# AIRZAI_LID_BD_REVC_Sheet1.net
KiCad netlist of a schematic drawn in Altium Designer
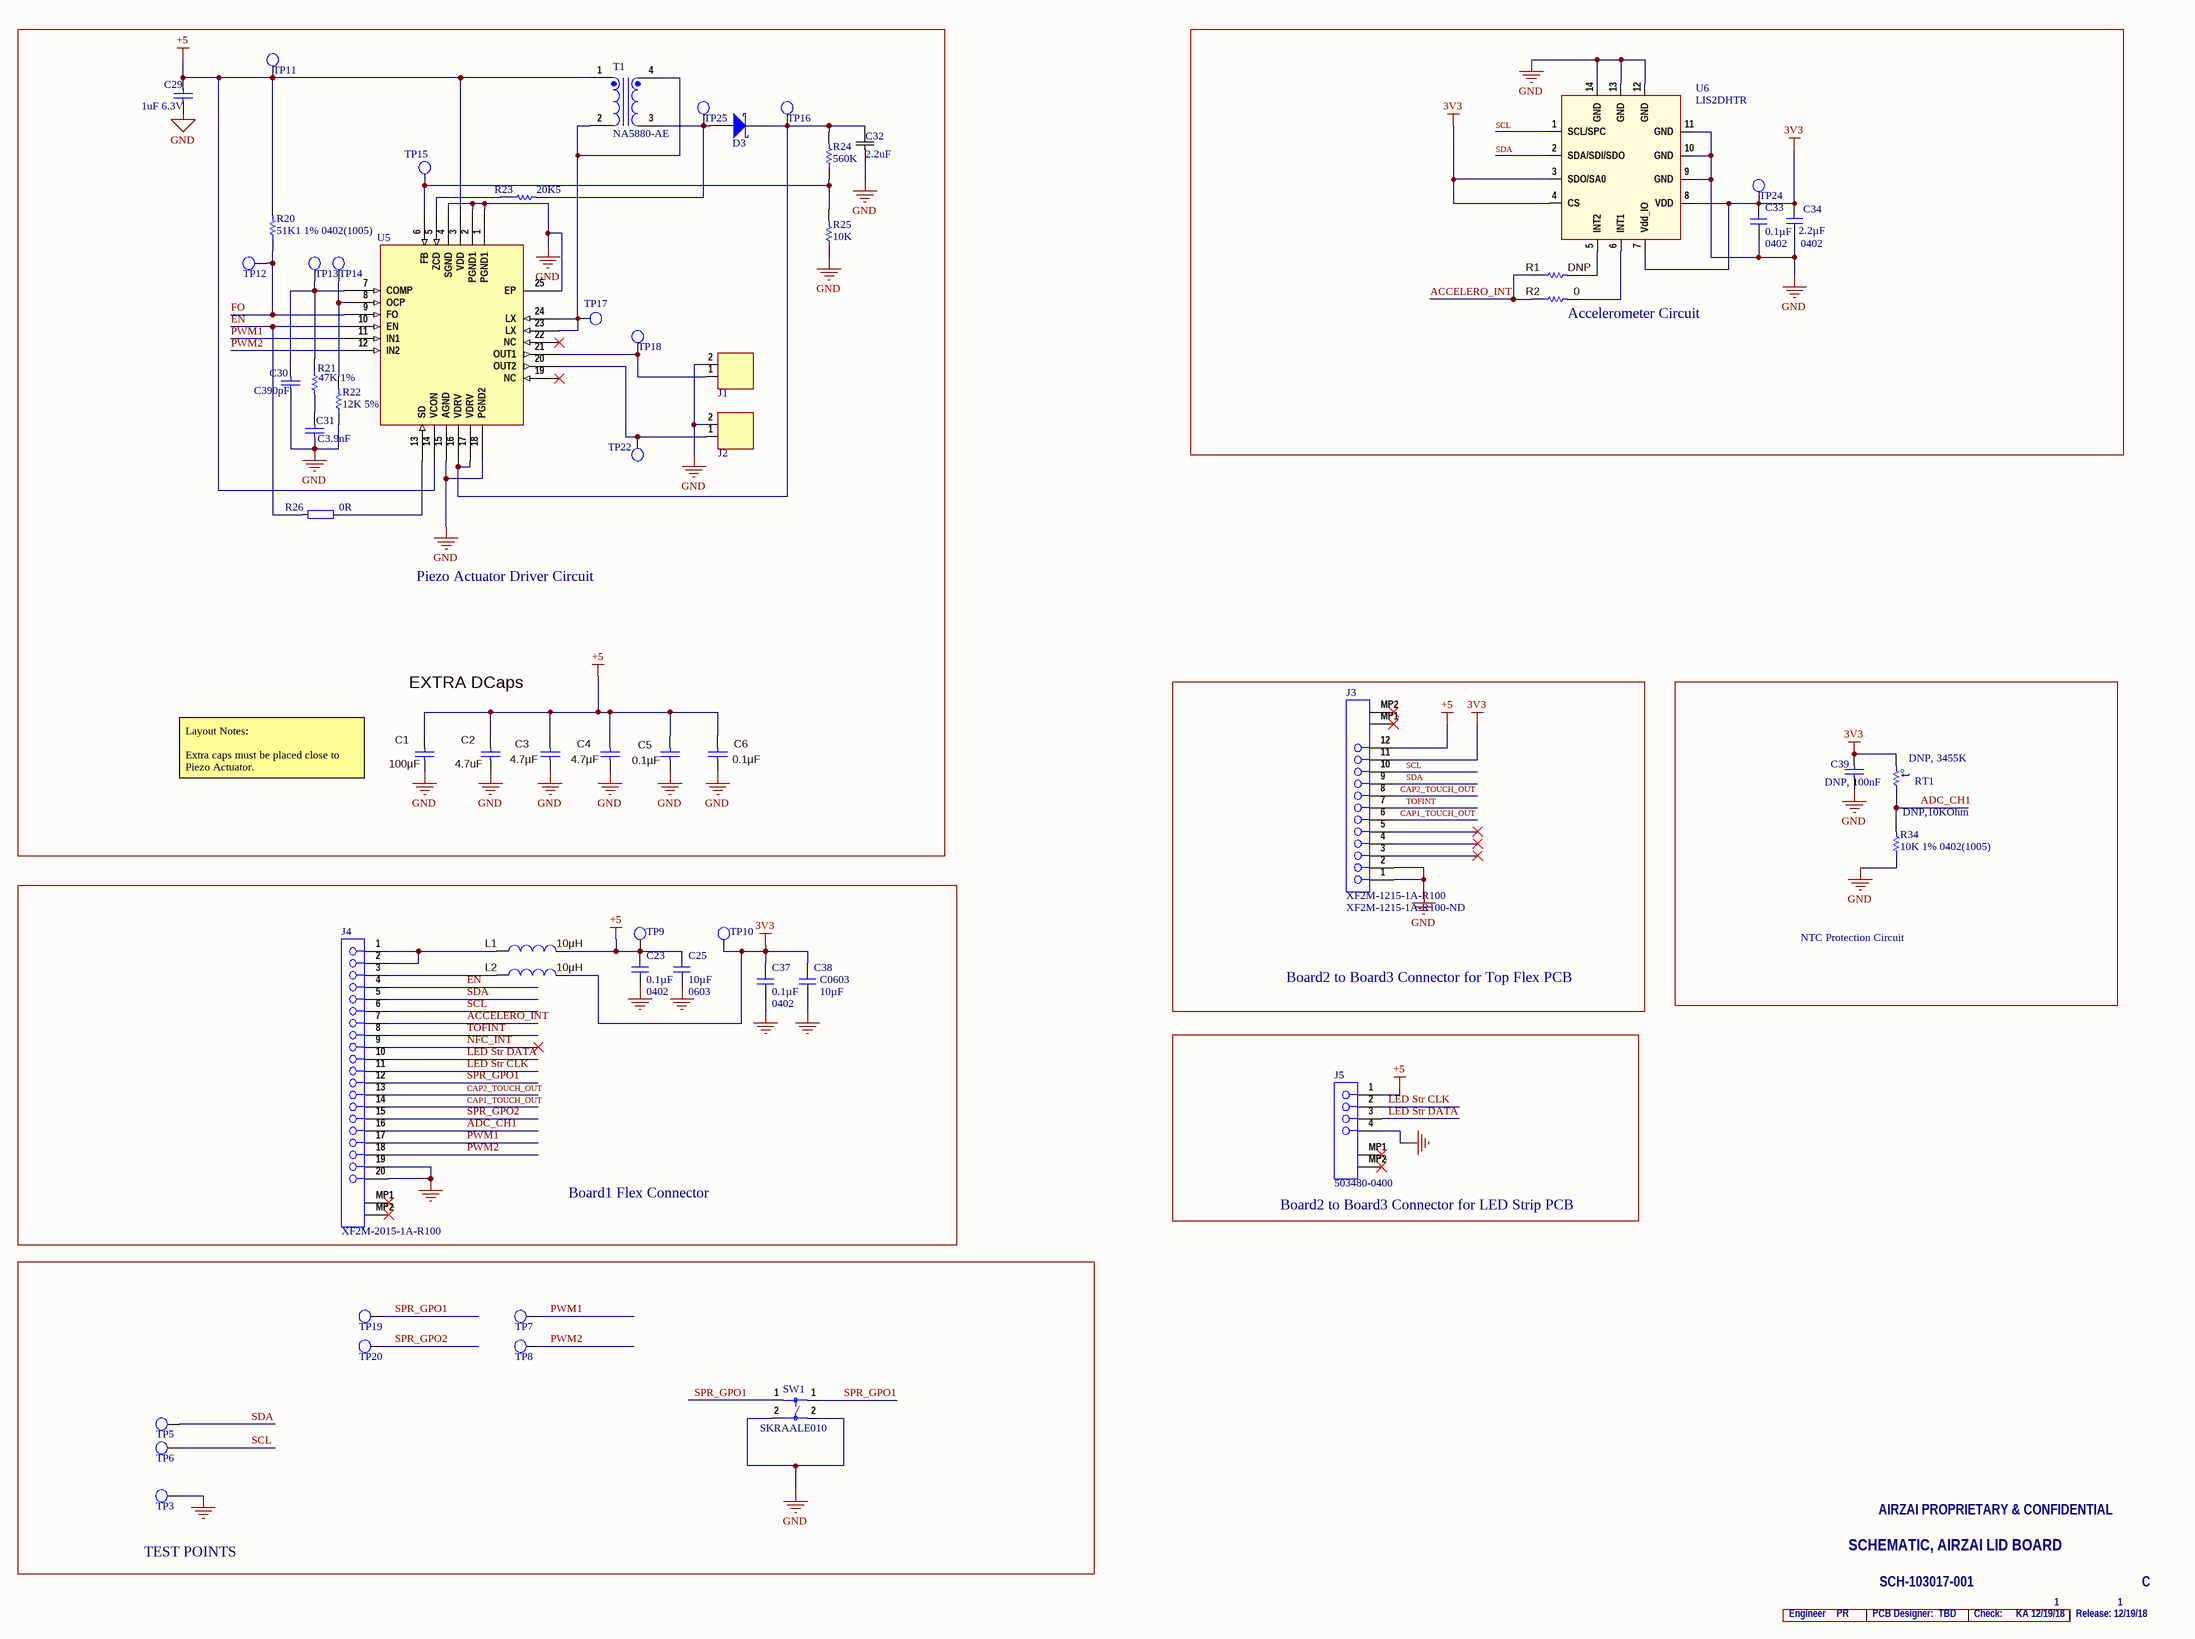
[diagram p0: AIRZAI_LID_BD_REVC Sheet1.SchDoc]

(export (version "E")
  (design (tool "Eeschema 10.0.6"))
  (components
    (comp (ref "C1")
      (value "GRM31CR60J107ME39L")
      (footprint "1206_180")
      (description "CAP, CERM, 100 µF, 6.3 V, +/- 20%, X5R, 1206")
      (fields
        (field (name "VALUEDISPLAYED") "100µF")
        (field (name "MANUFACTURER") "MuRata")
        (field (name "PUBLISHER") "Texas Instruments")
      )
      (libsource (lib "Capacitor_Ceramic") (part "GRM31CR60J107ME39L"))
    )
    (comp (ref "C2")
      (value "4.7uF")
      (footprint "SM0402_BTD.1SM_ACT_H55_CAP_WSS")
      (description "CAP, CERM, 4.7 µF, 6.3 V, +/- 20%, X5R, 0402")
      (fields (field (name "PARTNUMBER") "C1005X5R0J475M050BC") (field (name "MANUFACTURER") "TDK"))
      (libsource (lib "Capacitor_Ceramic") (part "C1005X5R0J475M050BC"))
    )
    (comp (ref "C3")
      (value "C1005X5R0J475M050BC")
      (footprint "SM0402_BTD.1SM_ACT_H55_CAP_WSS")
      (description "CAP, CERM, 4.7 µF, 6.3 V, +/- 20%, X5R, 0402")
      (fields
        (field (name "VALUEDISPLAYED") "4.7µF")
        (field (name "MANUFACTURER") "TDK")
        (field (name "PUBLISHER") "Texas Instruments")
      )
      (libsource (lib "Capacitor_Ceramic") (part "C1005X5R0J475M050BC"))
    )
    (comp (ref "C4")
      (value "C1005X5R0J475M050BC")
      (footprint "SM0402_BTD.1SM_ACT_H55_CAP_WSS")
      (description "CAP, CERM, 4.7 µF, 6.3 V, +/- 20%, X5R, 0402")
      (fields
        (field (name "VALUEDISPLAYED") "4.7µF")
        (field (name "MANUFACTURER") "TDK")
        (field (name "PUBLISHER") "Texas Instruments")
      )
      (libsource (lib "Capacitor_Ceramic") (part "C1005X5R0J475M050BC"))
    )
    (comp (ref "C5")
      (value "C1005X5R1A104K050BA")
      (footprint "SM0402_BTD.1SM_ACT_H55_CAP_WSS")
      (description "CAP, CERM, 0.1 µF, 10 V, +/- 10%, X5R, 0402")
      (fields
        (field (name "VALUEDISPLAYED") "0.1µF")
        (field (name "MANUFACTURER") "TDK")
        (field (name "PUBLISHER") "Texas Instruments")
      )
      (libsource (lib "Capacitor_Ceramic") (part "C1005X5R1A104K050BA"))
    )
    (comp (ref "C6")
      (value "C1005X5R1A104K050BA")
      (footprint "SM0402_BTD.1SM_ACT_H55_CAP_WSS")
      (description "CAP, CERM, 0.1 µF, 10 V, +/- 10%, X5R, 0402")
      (fields
        (field (name "VALUEDISPLAYED") "0.1µF")
        (field (name "MANUFACTURER") "TDK")
        (field (name "PUBLISHER") "Texas Instruments")
      )
      (libsource (lib "Capacitor_Ceramic") (part "C1005X5R1A104K050BA"))
    )
    (comp (ref "C23")
      (value "0.1µF")
      (footprint "0402")
      (description "Capacitor, X7R, ±10%")
      (fields (field (name "MANUFACTURER") "TDK") (field (name "MANUFACTURER PART NUMBER") "C1005X7R1C104K"))
      (libsource (lib "Nordic Passive DB") (part "CAP"))
    )
    (comp (ref "C25")
      (value "10µF")
      (footprint "0603")
      (description "6.3volts X5R 20%")
      (fields
        (field (name "MANUFACTURER") "MURATA")
        (field (name "MANUFACTURER PART NUMBER") "GRM188R60J106ME47D")
      )
      (libsource (lib "Nordic Passive DB") (part "CAP"))
    )
    (comp (ref "C29")
      (value "1uF 6.3V")
      (footprint "CAPC0402(1005)60_M")
      (description "CAP 1uF 6.3V ±10% 0402 (1005 Metric) Thickness 0.6mm SMD")
      (fields (field (name "TOLERANCE") "Â±10%") (field (name "MANUFACTURER") "MURATA"))
      (libsource (lib "AIRZAI_LID_BD_REVA") (part "CAP"))
    )
    (comp (ref "C30")
      (value "C390pF")
      (footprint "CAPC0402(1005)60_M")
      (description "CAP 390pF 50V ±20% 0402 (1005 Metric) Thickness 0.6mm SMD")
      (fields (field (name "TOLERANCE") "Â±20%") (field (name "MANUFACTURER") "KEMET"))
      (libsource (lib "") (part "CAP_1"))
    )
    (comp (ref "C31")
      (value "C3.9nF")
      (footprint "CAPC0402(1005)60_M")
      (description "CAP 3.9nF 50V ±10% 0402 (1005 Metric) Thickness 0.6mm SMD")
      (fields (field (name "TOLERANCE") "Â±10%") (field (name "MANUFACTURER") "TDK"))
      (libsource (lib "AIRZAI_LID_BD_REVA") (part "CAP"))
    )
    (comp (ref "C32")
      (value "2.2uF")
      (footprint "C1210_N")
      (description "Imported")
      (fields
        (field (name "MANUFACTURER_PART_NUMBER") "C3225JB2A225K230AB")
        (field (name "MANUFACTURER") "TDK")
      )
      (libsource (lib "C3225JB2A225K230AB") (part "C3225JB2A225K230"))
    )
    (comp (ref "C33")
      (value "0.1µF")
      (footprint "0402")
      (description "Capacitor, X7R, ±10%")
      (fields (field (name "MANUFACTURER") "TDK") (field (name "MANUFACTURER PART NUMBER") "C1005X7R1C104K"))
      (libsource (lib "Nordic Passive DB") (part "CAP"))
    )
    (comp (ref "C34")
      (value "2.2µF")
      (footprint "0402")
      (description "Capacitor, X7R, ±10%")
      (fields (field (name "MANUFACTURER") "TDK") (field (name "MANUFACTURER PART NUMBER") "C1005X5R0J225M"))
      (libsource (lib "Nordic Passive DB") (part "CAP"))
    )
    (comp (ref "C37")
      (value "0.1µF")
      (footprint "0402")
      (description "Capacitor, X7R, ±10%")
      (fields (field (name "MANUFACTURER") "TDK") (field (name "MANUFACTURER PART NUMBER") "C1005X7R1C104K"))
      (libsource (lib "Nordic Passive DB") (part "CAP"))
    )
    (comp (ref "C38")
      (value "10µF")
      (footprint "C0603")
      (description "Capacitor, X7R, ±10%")
      (fields
        (field (name "MANUFACTURER") "MURATA")
        (field (name "MANUFACTURER PART NUMBER") "GRM188R60J106ME47D")
      )
      (libsource (lib "Nordic Passive DB") (part "CAP"))
    )
    (comp (ref "C39")
      (value "DNP, 100nF")
      (footprint "CAPC0402(1005)60_M")
      (description "CAP 100nF 10V ±10% 0402 (1005 Metric) Thickness 0.6mm SMD")
      (fields (field (name "TOLERANCE") "Â±10%") (field (name "MANUFACTURER") "Yageo"))
      (libsource (lib "AIRZAI_LID_BD_REVA") (part "CAP"))
    )
    (comp (ref "D3")
      (value "STPS2H100A")
      (footprint "STM-SMA-2_V")
      (description "Power Schottky Rectifier, 2 A, 100 V, 2-Pin SMD (SMA), RoHS, Tape and Reel")
      (fields (field (name "MANUFACTURER") "STMicroelectronics"))
      (libsource (lib "AIRZAI_LID_BD_REVA") (part "DSKY-AK-2"))
    )
    (comp (ref "J1")
      (value "~")
      (footprint "CON_78171_0002")
      (fields (field (name "MANUFACTURER PART NUMBER") "781710002") (field (name "MANUFACTURER") "MOLEX"))
      (libsource (lib "DFM_JBKEGSVS_Library") (part "CONN_BM02B_SURS_TF"))
    )
    (comp (ref "J2")
      (value "~")
      (footprint "CON_78171_0002")
      (fields (field (name "MANUFACTURER PART NUMBER") "781710002") (field (name "MANUFACTURER") "MOLEX"))
      (libsource (lib "DFM_JBKEGSVS_Library") (part "CONN_BM02B_SURS_TF"))
    )
    (comp (ref "J3")
      (value "XF2M-1215-1A-R100")
      (footprint "Omron_XF2M-1215-1A-R100")
      (description "12 Position FPC Connector Contacts, Top and Bottom 0.020\" (0.50mm) Surface Mount, Right Angle")
      (fields
        (field (name "MANUFACTURER") "Omron")
        (field (name "SUPPLIER PART NUMBER 1") "XF2M-1215-1A-R100-ND")
      )
      (libsource (lib "AIRZAI_LID_BD_REVA") (part "XF2M-1215-1A-R100"))
    )
    (comp (ref "J4")
      (value "XF2M-2015-1A-R100")
      (footprint "Omron_XF2M-2015-1A_0")
      (fields (field (name "MANUFACTURER") "OMRON ELECTRONIC COMPONENTS"))
      (libsource (lib "AIRZAI_LID_BD_REVA") (part "XF2M-2015-1A-R100"))
    )
    (comp (ref "J5")
      (value "503480-0400")
      (footprint "MOLX-503480-0400")
      (fields (field (name "MANUFACTURER") "Molex"))
      (libsource (lib "AIRZAI_LID_BD_REVA") (part "503480-0400"))
    )
    (comp (ref "L1")
      (value "CB2012T100KR")
      (footprint "0805")
      (description "Inductor, 10 µH, 0.5A, 0.65 ohm, SMD")
      (fields
        (field (name "MANUFACTURER") "Taiyo Yuden")
        (field (name "TOLERANCE") "10%")
        (field (name "VALUEDISPLAYED") "10µH")
      )
      (libsource (lib "AIRZAI_LED_SENSE_FLEX_REVA") (part "CB2012T100KR"))
    )
    (comp (ref "L2")
      (value "CB2012T100KR")
      (footprint "0805")
      (description "Inductor, 10 µH, 0.5A, 0.65 ohm, SMD")
      (fields
        (field (name "MANUFACTURER") "Taiyo Yuden")
        (field (name "TOLERANCE") "10%")
        (field (name "VALUEDISPLAYED") "10µH")
      )
      (libsource (lib "AIRZAI_LED_SENSE_FLEX_REVA") (part "CB2012T100KR"))
    )
    (comp (ref "R1")
      (value "DNP")
      (footprint "0402")
      (description "RES, DNP, 0402")
      (libsource (lib "Resistor_0402") (part "ERJ-2GE0R00X"))
    )
    (comp (ref "R2")
      (value "ERJ-2GE0R00X")
      (footprint "0402")
      (description "RES, 0, 5%, 0.063 W, 0402")
      (fields
        (field (name "VALUEDISPLAYED") "0")
        (field (name "MANUFACTURER") "Panasonic")
        (field (name "PUBLISHER") "Texas Instruments")
      )
      (libsource (lib "Resistor_0402") (part "ERJ-2GE0R00X"))
    )
    (comp (ref "R20")
      (value "51K1 1% 0402(1005)")
      (footprint "0402")
      (description "51K1 0.063W 1% 0402 (1005 Metric)  SMD")
      (fields (field (name "POWER") "0.063 W") (field (name "TOLERANCE") "1 %"))
      (libsource (lib "AIRZAI_LID_BD_REVA") (part "RES"))
    )
    (comp (ref "R21")
      (value "47K 1%")
      (footprint "0402")
      (description "47K 0.063W 1% 0402 (1005 Metric)  SMD")
      (fields (field (name "POWER") "0.063 W") (field (name "TOLERANCE") "1 %"))
      (libsource (lib "") (part "RES_2"))
    )
    (comp (ref "R22")
      (value "12K 5%")
      (footprint "0402")
      (description "12K 0.063W 5% 0402 (1005 Metric)  SMD")
      (fields (field (name "TOLERANCE") "5 %") (field (name "POWER") "0.063 W"))
      (libsource (lib "AIRZAI_LID_BD_REVA") (part "RES"))
    )
    (comp (ref "R23")
      (value "20K5")
      (footprint "0402")
      (description "20K5 0.063W 1% 0402 (1005 Metric)  SMD")
      (fields (field (name "POWER") "0.063 W") (field (name "TOLERANCE") "1 %"))
      (libsource (lib "") (part "RES_1"))
    )
    (comp (ref "R24")
      (value "560K")
      (footprint "0402")
      (description "560K 0.063W 1% 0402 (1005 Metric)  SMD")
      (fields (field (name "POWER") "0.063 W") (field (name "TOLERANCE") "1 %"))
      (libsource (lib "AIRZAI_LID_BD_REVA") (part "RES"))
    )
    (comp (ref "R25")
      (value "10K")
      (footprint "0402")
      (description "10K 0.063W 5% 0402 (1005 Metric)  SMD")
      (fields (field (name "TOLERANCE") "5 %") (field (name "POWER") "0.063 W"))
      (libsource (lib "AIRZAI_LID_BD_REVA") (part "RES"))
    )
    (comp (ref "R26")
      (value "0R")
      (footprint "0402")
      (description "Resistor, ±1%, 0.063W")
      (fields
        (field (name "MANUFACTURER") "Panasonic")
        (field (name "MANUFACTURER PART NUMBER") "ERJ-2GE0R00X")
      )
      (libsource (lib "Nordic Passive DB") (part "RES_1"))
    )
    (comp (ref "R34")
      (value "10K 1% 0402(1005)")
      (footprint "0402")
      (description "10K 0.063W 1% 0402 (1005 Metric)  SMD")
      (fields
        (field (name "ALTIUM_VALUE") "DNP,10KOhm")
        (field (name "TOLERANCE") "1 %")
        (field (name "POWER") "0.063 W")
      )
      (libsource (lib "AIRZAI_LID_BD_REVA") (part "RES"))
    )
    (comp (ref "RT1")
      (value "DNP, 3455K")
      (footprint "MURA-NCP18XH103F03RB-2_V")
      (description "NTC Thermistor, 10 KOhm, +/- 1%, 0.1 W, -40 to 125 degC, 0603 (1608 Metric), RoHS, Tape and Reel")
      (fields
        (field (name "MANUFACTURER") "Murata")
        (field (name "MANUFACTURER PART NUMBER") "NCP18XH103F03RB")
      )
      (libsource (lib "AIRZAI_LID_BD_REVA") (part "MURA-NCP18XH103F03RB-2"))
    )
    (comp (ref "SW1")
      (value "SKRAALE010")
      (footprint "SW_ALPS_SKRAALE010")
      (fields (field (name "MANUFACTURER") "ALPS") (field (name "MANUFACTURER PART NUMBER") "SKRAAKE010"))
      (libsource (lib "DFM_JBKEGSVS_Library") (part "SW_SKRAALE010"))
    )
    (comp (ref "T1")
      (value "NA5880-AE")
      (footprint "Coilcraft_NA5880-AE_MFG")
      (fields (field (name "MANUFACTURER") "CoilCraft") (field (name "TOLERANCE") "20%"))
      (libsource (lib "AIRZAI_LID_BD_REVA") (part "TRANS-DOT-1-1-4"))
    )
    (comp (ref "TP3")
      (value "TESTPOINT")
      (footprint "TP_0.9MM")
      (libsource (lib "DFM_JBKEGSVS_Library") (part "TESTPOINT"))
    )
    (comp (ref "TP5")
      (value "TESTPOINT")
      (footprint "TP_0.9MM")
      (libsource (lib "DFM_JBKEGSVS_Library") (part "TESTPOINT"))
    )
    (comp (ref "TP6")
      (value "TESTPOINT")
      (footprint "TP_0.9MM")
      (libsource (lib "DFM_JBKEGSVS_Library") (part "TESTPOINT"))
    )
    (comp (ref "TP7")
      (value "TESTPOINT")
      (footprint "TP_0.9MM")
      (libsource (lib "DFM_JBKEGSVS_Library") (part "TESTPOINT"))
    )
    (comp (ref "TP8")
      (value "TESTPOINT")
      (footprint "TP_0.9MM")
      (libsource (lib "DFM_JBKEGSVS_Library") (part "TESTPOINT"))
    )
    (comp (ref "TP9")
      (value "TESTPOINT")
      (footprint "TP_0.9MM")
      (libsource (lib "DFM_JBKEGSVS_Library") (part "TESTPOINT"))
    )
    (comp (ref "TP10")
      (value "TESTPOINT")
      (footprint "TP_0.9MM")
      (libsource (lib "DFM_JBKEGSVS_Library") (part "TESTPOINT"))
    )
    (comp (ref "TP11")
      (value "TESTPOINT")
      (footprint "TP_0.9MM")
      (libsource (lib "AIRZAI_LID_BD_REVA") (part "TESTPOINT"))
    )
    (comp (ref "TP12")
      (value "TESTPOINT")
      (footprint "TP_0.9MM")
      (libsource (lib "AIRZAI_LID_BD_REVA") (part "TESTPOINT"))
    )
    (comp (ref "TP13")
      (value "TESTPOINT")
      (footprint "TP_0.9MM")
      (libsource (lib "AIRZAI_LID_BD_REVA") (part "TESTPOINT"))
    )
    (comp (ref "TP14")
      (value "TESTPOINT")
      (footprint "TP_0.9MM")
      (libsource (lib "AIRZAI_LID_BD_REVA") (part "TESTPOINT"))
    )
    (comp (ref "TP15")
      (value "TESTPOINT")
      (footprint "TP_0.9MM")
      (libsource (lib "AIRZAI_LID_BD_REVA") (part "TESTPOINT"))
    )
    (comp (ref "TP16")
      (value "TESTPOINT")
      (footprint "TP_0.9MM")
      (libsource (lib "AIRZAI_LID_BD_REVA") (part "TESTPOINT"))
    )
    (comp (ref "TP17")
      (value "TESTPOINT")
      (footprint "TP_0.9MM")
      (libsource (lib "AIRZAI_LID_BD_REVA") (part "TESTPOINT"))
    )
    (comp (ref "TP18")
      (value "TESTPOINT")
      (footprint "TP_0.9MM")
      (libsource (lib "AIRZAI_LID_BD_REVA") (part "TESTPOINT"))
    )
    (comp (ref "TP19")
      (value "TESTPOINT")
      (footprint "TP_0.9MM")
      (libsource (lib "DFM_JBKEGSVS_Library") (part "TESTPOINT"))
    )
    (comp (ref "TP20")
      (value "TESTPOINT")
      (footprint "TP_0.9MM")
      (libsource (lib "DFM_JBKEGSVS_Library") (part "TESTPOINT"))
    )
    (comp (ref "TP22")
      (value "TESTPOINT")
      (footprint "TP_0.9MM")
      (libsource (lib "AIRZAI_LID_BD_REVA") (part "TESTPOINT"))
    )
    (comp (ref "TP24")
      (value "TESTPOINT")
      (footprint "TP_0.9MM")
      (libsource (lib "AIRZAI_LID_BD_REVA") (part "TESTPOINT"))
    )
    (comp (ref "TP25")
      (value "TESTPOINT")
      (footprint "TP_0.9MM")
      (libsource (lib "AIRZAI_LID_BD_REVA") (part "TESTPOINT"))
    )
    (comp (ref "U5")
      (value "FAN8841MPXCT-ND")
      (footprint "WFQFN-24-FAN8841MPX")
      (description "IC PIEZO ACTUATOR DVR 24MLP")
      (fields
        (field (name "MANUFACTURER") "ON Semiconductor")
        (field (name "MANUFACTURER PART NUMBER") "FAN8841MPX")
      )
      (libsource (lib "AIRZAI_LID_BD_REVA") (part "FAN8841MPXCT-ND"))
    )
    (comp (ref "U6")
      (value "LIS2DHTR")
      (footprint "STM-LGA-14_L")
      (fields (field (name "MANUFACTURER") "ST"))
      (libsource (lib "AIRZAI_LID_BD_REVA") (part "LIS2DH"))
    )
  )
  (nets
    (net (code "1") (name "+5") (class "Default")
      (node (ref "C1") (pin "1") (pinfunction "1_1") (pintype "passive"))
      (node (ref "C2") (pin "1") (pinfunction "1_1") (pintype "passive"))
      (node (ref "C23") (pin "1") (pinfunction "1_1") (pintype "passive"))
      (node (ref "C25") (pin "1") (pinfunction "1_1") (pintype "passive"))
      (node (ref "C29") (pin "2") (pinfunction "2_2") (pintype "passive"))
      (node (ref "C3") (pin "1") (pinfunction "1_1") (pintype "passive"))
      (node (ref "C4") (pin "1") (pinfunction "1_1") (pintype "passive"))
      (node (ref "C5") (pin "1") (pinfunction "1_1") (pintype "passive"))
      (node (ref "C6") (pin "1") (pinfunction "1_1") (pintype "passive"))
      (node (ref "J3") (pin "12") (pinfunction "12_12") (pintype "passive"))
      (node (ref "J5") (pin "1") (pinfunction "1_1") (pintype "passive"))
      (node (ref "L1") (pin "2") (pinfunction "2_2") (pintype "passive"))
      (node (ref "R20") (pin "2") (pinfunction "2_2") (pintype "passive"))
      (node (ref "T1") (pin "1") (pinfunction "1_1") (pintype "passive"))
      (node (ref "TP11") (pin "1") (pinfunction "1_1") (pintype "passive"))
      (node (ref "TP9") (pin "1") (pinfunction "1_1") (pintype "passive"))
      (node (ref "U5") (pin "14") (pinfunction "VCON_14") (pintype "power_in"))
      (node (ref "U5") (pin "3") (pinfunction "VDD_3") (pintype "power_in"))
    )
    (net (code "2") (name "/ACCELERO_INT") (class "Default")
      (node (ref "J4") (pin "7") (pinfunction "7_7") (pintype "passive"))
      (node (ref "R1") (pin "1") (pinfunction "1_1") (pintype "passive"))
      (node (ref "R2") (pin "1") (pinfunction "1_1") (pintype "passive"))
    )
    (net (code "3") (name "/ADC_CH1") (class "Default")
      (node (ref "J4") (pin "16") (pinfunction "16_16") (pintype "passive"))
      (node (ref "R34") (pin "2") (pinfunction "2_2") (pintype "passive"))
      (node (ref "RT1") (pin "1") (pinfunction "1_1") (pintype "passive"))
    )
    (net (code "4") (name "/CAP1_TOUCH_OUT") (class "Default")
      (node (ref "J3") (pin "6") (pinfunction "6_6") (pintype "passive"))
      (node (ref "J4") (pin "14") (pinfunction "14_14") (pintype "passive"))
    )
    (net (code "5") (name "/CAP2_TOUCH_OUT") (class "Default")
      (node (ref "J3") (pin "8") (pinfunction "8_8") (pintype "passive"))
      (node (ref "J4") (pin "13") (pinfunction "13_13") (pintype "passive"))
    )
    (net (code "6") (name "/EN") (class "Default")
      (node (ref "J4") (pin "4") (pinfunction "4_4") (pintype "passive"))
      (node (ref "R26") (pin "2") (pinfunction "2_2") (pintype "passive"))
      (node (ref "U5") (pin "10") (pinfunction "EN_10") (pintype "input"))
    )
    (net (code "7") (name "/FO") (class "Default")
      (node (ref "R20") (pin "1") (pinfunction "1_1") (pintype "passive"))
      (node (ref "TP12") (pin "1") (pinfunction "1_1") (pintype "passive"))
      (node (ref "U5") (pin "9") (pinfunction "FO_9") (pintype "input"))
    )
    (net (code "8") (name "/LED Str CLK") (class "Default")
      (node (ref "J4") (pin "11") (pinfunction "11_11") (pintype "passive"))
      (node (ref "J5") (pin "2") (pinfunction "2_2") (pintype "passive"))
    )
    (net (code "9") (name "/LED Str DATA") (class "Default")
      (node (ref "J4") (pin "10") (pinfunction "10_10") (pintype "passive"))
      (node (ref "J5") (pin "3") (pinfunction "3_3") (pintype "passive"))
    )
    (net (code "10") (name "/NFC_INT") (class "Default")
      (node (ref "J4") (pin "9") (pinfunction "9_9") (pintype "passive+no_connect"))
    )
    (net (code "11") (name "/PWM1") (class "Default")
      (node (ref "J4") (pin "17") (pinfunction "17_17") (pintype "passive"))
      (node (ref "TP7") (pin "1") (pinfunction "1_1") (pintype "passive"))
      (node (ref "U5") (pin "11") (pinfunction "IN1_11") (pintype "input"))
    )
    (net (code "12") (name "/PWM2") (class "Default")
      (node (ref "J4") (pin "18") (pinfunction "18_18") (pintype "passive"))
      (node (ref "TP8") (pin "1") (pinfunction "1_1") (pintype "passive"))
      (node (ref "U5") (pin "12") (pinfunction "IN2_12") (pintype "input"))
    )
    (net (code "13") (name "/SCL") (class "Default")
      (node (ref "J3") (pin "10") (pinfunction "10_10") (pintype "passive"))
      (node (ref "J4") (pin "6") (pinfunction "6_6") (pintype "passive"))
      (node (ref "TP6") (pin "1") (pinfunction "1_1") (pintype "passive"))
      (node (ref "U6") (pin "1") (pinfunction "SCL/SPC_1") (pintype "passive"))
    )
    (net (code "14") (name "/SDA") (class "Default")
      (node (ref "J3") (pin "9") (pinfunction "9_9") (pintype "passive"))
      (node (ref "J4") (pin "5") (pinfunction "5_5") (pintype "passive"))
      (node (ref "TP5") (pin "1") (pinfunction "1_1") (pintype "passive"))
      (node (ref "U6") (pin "2") (pinfunction "SDA/SDI/SDO_2") (pintype "passive"))
    )
    (net (code "15") (name "/SPR_GPO1") (class "Default")
      (node (ref "J4") (pin "12") (pinfunction "12_12") (pintype "passive"))
      (node (ref "SW1") (pin "1") (pinfunction "1_1") (pintype "passive"))
      (node (ref "TP19") (pin "1") (pinfunction "1_1") (pintype "passive"))
    )
    (net (code "16") (name "/SPR_GPO2") (class "Default")
      (node (ref "J4") (pin "15") (pinfunction "15_15") (pintype "passive"))
      (node (ref "TP20") (pin "1") (pinfunction "1_1") (pintype "passive"))
    )
    (net (code "17") (name "/TOFINT") (class "Default")
      (node (ref "J3") (pin "7") (pinfunction "7_7") (pintype "passive"))
      (node (ref "J4") (pin "8") (pinfunction "8_8") (pintype "passive"))
    )
    (net (code "18") (name "3V3") (class "Default")
      (node (ref "C33") (pin "1") (pinfunction "1_1") (pintype "passive"))
      (node (ref "C34") (pin "2") (pinfunction "2_2") (pintype "passive"))
      (node (ref "C37") (pin "1") (pinfunction "1_1") (pintype "passive"))
      (node (ref "C38") (pin "1") (pinfunction "1_1") (pintype "passive"))
      (node (ref "C39") (pin "2") (pinfunction "2_2") (pintype "passive"))
      (node (ref "J3") (pin "11") (pinfunction "11_11") (pintype "passive"))
      (node (ref "L2") (pin "2") (pinfunction "2_2") (pintype "passive"))
      (node (ref "RT1") (pin "2") (pinfunction "2_2") (pintype "passive"))
      (node (ref "TP10") (pin "1") (pinfunction "1_1") (pintype "passive"))
      (node (ref "TP24") (pin "1") (pinfunction "1_1") (pintype "passive"))
      (node (ref "U6") (pin "3") (pinfunction "SDO/SA0_3") (pintype "passive"))
      (node (ref "U6") (pin "4") (pinfunction "CS_4") (pintype "passive"))
      (node (ref "U6") (pin "7") (pinfunction "Vdd_IO_7") (pintype "passive"))
      (node (ref "U6") (pin "8") (pinfunction "VDD_8") (pintype "passive"))
    )
    (net (code "19") (name "GND") (class "Default")
      (node (ref "C1") (pin "2") (pinfunction "2_2") (pintype "passive"))
      (node (ref "C2") (pin "2") (pinfunction "2_2") (pintype "passive"))
      (node (ref "C23") (pin "2") (pinfunction "2_2") (pintype "passive"))
      (node (ref "C25") (pin "2") (pinfunction "2_2") (pintype "passive"))
      (node (ref "C29") (pin "1") (pinfunction "1_1") (pintype "passive"))
      (node (ref "C3") (pin "2") (pinfunction "2_2") (pintype "passive"))
      (node (ref "C30") (pin "2") (pinfunction "2_2") (pintype "passive"))
      (node (ref "C31") (pin "1") (pinfunction "1_1") (pintype "passive"))
      (node (ref "C32") (pin "1") (pinfunction "1_1") (pintype "passive"))
      (node (ref "C33") (pin "2") (pinfunction "2_2") (pintype "passive"))
      (node (ref "C34") (pin "1") (pinfunction "1_1") (pintype "passive"))
      (node (ref "C37") (pin "2") (pinfunction "2_2") (pintype "passive"))
      (node (ref "C38") (pin "2") (pinfunction "2_2") (pintype "passive"))
      (node (ref "C39") (pin "1") (pinfunction "1_1") (pintype "passive"))
      (node (ref "C4") (pin "2") (pinfunction "2_2") (pintype "passive"))
      (node (ref "C5") (pin "2") (pinfunction "2_2") (pintype "passive"))
      (node (ref "C6") (pin "2") (pinfunction "2_2") (pintype "passive"))
      (node (ref "J1") (pin "2") (pinfunction "2_2") (pintype "passive"))
      (node (ref "J2") (pin "2") (pinfunction "2_2") (pintype "passive"))
      (node (ref "J3") (pin "1") (pinfunction "1_1") (pintype "passive"))
      (node (ref "J3") (pin "2") (pinfunction "2_2") (pintype "passive"))
      (node (ref "J4") (pin "19") (pinfunction "19_19") (pintype "passive"))
      (node (ref "J4") (pin "20") (pinfunction "20_20") (pintype "passive"))
      (node (ref "J5") (pin "4") (pinfunction "4_4") (pintype "passive"))
      (node (ref "R22") (pin "1") (pinfunction "1_1") (pintype "passive"))
      (node (ref "R25") (pin "1") (pinfunction "1_1") (pintype "passive"))
      (node (ref "R34") (pin "1") (pinfunction "1_1") (pintype "passive"))
      (node (ref "SW1") (pin "2") (pinfunction "2_2") (pintype "passive"))
      (node (ref "TP3") (pin "1") (pinfunction "1_1") (pintype "passive"))
      (node (ref "U5") (pin "1") (pinfunction "PGND1_1") (pintype "power_in"))
      (node (ref "U5") (pin "15") (pinfunction "AGND_15") (pintype "power_in"))
      (node (ref "U5") (pin "18") (pinfunction "PGND2_18") (pintype "power_in"))
      (node (ref "U5") (pin "2") (pinfunction "PGND1_2") (pintype "power_in"))
      (node (ref "U5") (pin "25") (pinfunction "EP_25") (pintype "passive"))
      (node (ref "U5") (pin "4") (pinfunction "SGND_4") (pintype "power_in"))
      (node (ref "U6") (pin "10") (pinfunction "GND_10") (pintype "passive"))
      (node (ref "U6") (pin "11") (pinfunction "GND_11") (pintype "passive"))
      (node (ref "U6") (pin "12") (pinfunction "GND_12") (pintype "passive"))
      (node (ref "U6") (pin "13") (pinfunction "GND_13") (pintype "passive"))
      (node (ref "U6") (pin "14") (pinfunction "GND_14") (pintype "passive"))
      (node (ref "U6") (pin "9") (pinfunction "GND_9") (pintype "passive"))
    )
    (net (code "20") (name "Net-(C31-Pad2)") (class "Default")
      (node (ref "C31") (pin "2") (pinfunction "2_2") (pintype "passive"))
      (node (ref "R21") (pin "2") (pinfunction "2_2") (pintype "passive"))
    )
    (net (code "21") (name "Net-(D3-A)") (class "Default")
      (node (ref "D3") (pin "1") (pinfunction "A_1") (pintype "passive"))
      (node (ref "R23") (pin "2") (pinfunction "2_2") (pintype "passive"))
      (node (ref "T1") (pin "3") (pinfunction "3_3") (pintype "passive"))
      (node (ref "TP25") (pin "1") (pinfunction "1_1") (pintype "passive"))
    )
    (net (code "22") (name "Net-(D3-K)") (class "Default")
      (node (ref "C32") (pin "2") (pinfunction "2_2") (pintype "passive"))
      (node (ref "D3") (pin "2") (pinfunction "K_2") (pintype "passive"))
      (node (ref "R24") (pin "2") (pinfunction "2_2") (pintype "passive"))
      (node (ref "TP16") (pin "1") (pinfunction "1_1") (pintype "passive"))
      (node (ref "U5") (pin "16") (pinfunction "VDRV_16") (pintype "power_in"))
      (node (ref "U5") (pin "17") (pinfunction "VDRV_17") (pintype "power_in"))
    )
    (net (code "23") (name "Net-(J4-Pad1)") (class "Default")
      (node (ref "J4") (pin "1") (pinfunction "1_1") (pintype "passive"))
      (node (ref "J4") (pin "2") (pinfunction "2_2") (pintype "passive"))
      (node (ref "L1") (pin "1") (pinfunction "1_1") (pintype "passive"))
    )
    (net (code "24") (name "Net-(J4-Pad3)") (class "Default")
      (node (ref "J4") (pin "3") (pinfunction "3_3") (pintype "passive"))
      (node (ref "L2") (pin "1") (pinfunction "1_1") (pintype "passive"))
    )
    (net (code "25") (name "Net-(T1-Pad2)") (class "Default")
      (node (ref "T1") (pin "2") (pinfunction "2_2") (pintype "passive"))
      (node (ref "T1") (pin "4") (pinfunction "4_4") (pintype "passive"))
      (node (ref "TP17") (pin "1") (pinfunction "1_1") (pintype "passive"))
      (node (ref "U5") (pin "23") (pinfunction "LX_23") (pintype "input"))
      (node (ref "U5") (pin "24") (pinfunction "LX_24") (pintype "input"))
    )
    (net (code "26") (name "Net-(U5-COMP)") (class "Default")
      (node (ref "C30") (pin "1") (pinfunction "1_1") (pintype "passive"))
      (node (ref "R21") (pin "1") (pinfunction "1_1") (pintype "passive"))
      (node (ref "TP13") (pin "1") (pinfunction "1_1") (pintype "passive"))
      (node (ref "U5") (pin "7") (pinfunction "COMP_7") (pintype "input"))
    )
    (net (code "27") (name "Net-(U5-FB)") (class "Default")
      (node (ref "R24") (pin "1") (pinfunction "1_1") (pintype "passive"))
      (node (ref "R25") (pin "2") (pinfunction "2_2") (pintype "passive"))
      (node (ref "TP15") (pin "1") (pinfunction "1_1") (pintype "passive"))
      (node (ref "U5") (pin "6") (pinfunction "FB_6") (pintype "input"))
    )
    (net (code "28") (name "Net-(U5-OCP)") (class "Default")
      (node (ref "R22") (pin "2") (pinfunction "2_2") (pintype "passive"))
      (node (ref "TP14") (pin "1") (pinfunction "1_1") (pintype "passive"))
      (node (ref "U5") (pin "8") (pinfunction "OCP_8") (pintype "input"))
    )
    (net (code "29") (name "Net-(U5-OUT1)") (class "Default")
      (node (ref "J1") (pin "1") (pinfunction "1_1") (pintype "passive"))
      (node (ref "TP18") (pin "1") (pinfunction "1_1") (pintype "passive"))
      (node (ref "U5") (pin "21") (pinfunction "OUT1_21") (pintype "output"))
    )
    (net (code "30") (name "Net-(U5-OUT2)") (class "Default")
      (node (ref "J2") (pin "1") (pinfunction "1_1") (pintype "passive"))
      (node (ref "TP22") (pin "1") (pinfunction "1_1") (pintype "passive"))
      (node (ref "U5") (pin "20") (pinfunction "OUT2_20") (pintype "output"))
    )
    (net (code "31") (name "Net-(U5-SD)") (class "Default")
      (node (ref "R26") (pin "1") (pinfunction "1_1") (pintype "passive"))
      (node (ref "U5") (pin "13") (pinfunction "SD_13") (pintype "input"))
    )
    (net (code "32") (name "Net-(U5-ZCD)") (class "Default")
      (node (ref "R23") (pin "1") (pinfunction "1_1") (pintype "passive"))
      (node (ref "U5") (pin "5") (pinfunction "ZCD_5") (pintype "input"))
    )
    (net (code "33") (name "Net-(U6-INT1)") (class "Default")
      (node (ref "R2") (pin "2") (pinfunction "2_2") (pintype "passive"))
      (node (ref "U6") (pin "6") (pinfunction "INT1_6") (pintype "passive"))
    )
    (net (code "34") (name "Net-(U6-INT2)") (class "Default")
      (node (ref "R1") (pin "2") (pinfunction "2_2") (pintype "passive"))
      (node (ref "U6") (pin "5") (pinfunction "INT2_5") (pintype "passive"))
    )
    (net (code "35") (name "unconnected-(J3-Pad3)") (class "Default")
      (node (ref "J3") (pin "3") (pinfunction "3_3") (pintype "passive+no_connect"))
    )
    (net (code "36") (name "unconnected-(J3-Pad4)") (class "Default")
      (node (ref "J3") (pin "4") (pinfunction "4_4") (pintype "passive+no_connect"))
    )
    (net (code "37") (name "unconnected-(J3-Pad5)") (class "Default")
      (node (ref "J3") (pin "5") (pinfunction "5_5") (pintype "passive+no_connect"))
    )
    (net (code "38") (name "unconnected-(J3-PadMP1)") (class "Default")
      (node (ref "J3") (pin "MP1") (pinfunction "MP1_MP1") (pintype "passive+no_connect"))
    )
    (net (code "39") (name "unconnected-(J3-PadMP2)") (class "Default")
      (node (ref "J3") (pin "MP2") (pinfunction "MP2_MP2") (pintype "passive+no_connect"))
    )
    (net (code "40") (name "unconnected-(J4-PadMP1)") (class "Default")
      (node (ref "J4") (pin "MP1") (pinfunction "MP1_MP1") (pintype "passive+no_connect"))
    )
    (net (code "41") (name "unconnected-(J4-PadMP2)") (class "Default")
      (node (ref "J4") (pin "MP2") (pinfunction "MP2_MP2") (pintype "passive+no_connect"))
    )
    (net (code "42") (name "unconnected-(J5-PadMP1)") (class "Default")
      (node (ref "J5") (pin "MP1") (pinfunction "MP1_MP1") (pintype "passive+no_connect"))
    )
    (net (code "43") (name "unconnected-(J5-PadMP2)") (class "Default")
      (node (ref "J5") (pin "MP2") (pinfunction "MP2_MP2") (pintype "passive+no_connect"))
    )
    (net (code "44") (name "unconnected-(U5-NC-Pad19)") (class "Default")
      (node (ref "U5") (pin "19") (pinfunction "NC_19") (pintype "input+no_connect"))
    )
    (net (code "45") (name "unconnected-(U5-NC-Pad22)") (class "Default")
      (node (ref "U5") (pin "22") (pinfunction "NC_22") (pintype "input+no_connect"))
    )
  )
)
